# 7_Airframe-Sensors.net
KiCad netlist of a schematic drawn in Altium Designer
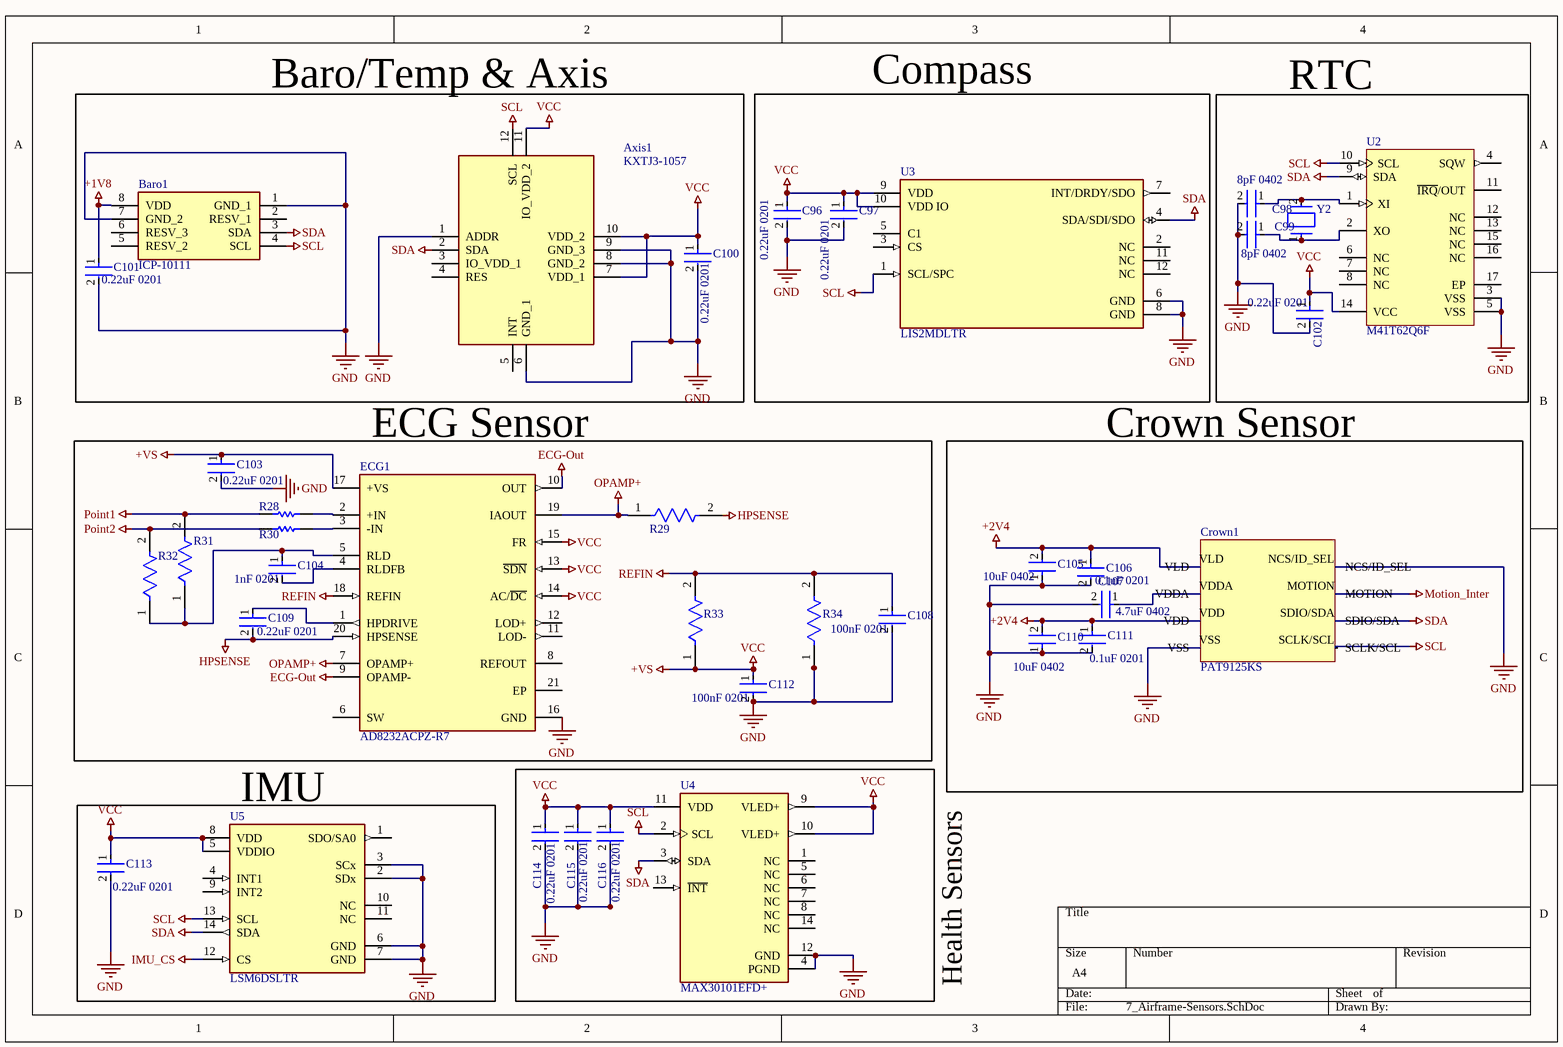
[diagram p0: 7_Airframe-Sensors.SchDoc]

(export (version "E")
  (design (tool "Eeschema 10.0.6"))
  (components
    (comp (ref "Axis1")
      (value "KXTJ3-1057")
      (footprint "SamacSys:2X2X0.9MMLGA")
      (description "Accelerometer")
      (fields (field (name "MOUSER PART NUMBER") "912-KXTJ3-1057"))
      (libsource (lib "*") (part "KXTJ3-1057"))
    )
    (comp (ref "Baro1")
      (value "ICP-10111")
      (footprint "SamacSys:ICP10111")
      (description "Undefined or Miscellaneous")
      (fields (field (name "MOUSER PART NUMBER") "410-ICP-10111"))
      (libsource (lib "*") (part "ICP-10111"))
    )
    (comp (ref "C96")
      (value "0.22uF 0201")
      (footprint "FP-C0603-030-0_03-IPC_C")
      (description "Multilayer Ceramic Capacitors 220nF ±10% 6.3V X6S SMD 0201")
      (fields (field (name "TOLERANCE") "10%"))
      (libsource (lib "Altium Content Vault") (part "02cd4be3c70576c341d710602a673aa"))
    )
    (comp (ref "C97")
      (value "0.22uF 0201")
      (footprint "FP-C0603-030-0_03-IPC_C")
      (description "Multilayer Ceramic Capacitors 220nF ±10% 6.3V X6S SMD 0201")
      (fields (field (name "TOLERANCE") "10%"))
      (libsource (lib "Altium Content Vault") (part "02cd4be3c70576c341d710602a673aa"))
    )
    (comp (ref "C98")
      (value "8pF 0402")
      (footprint "FP-C0402C225M9PACTU-MFG")
      (description "CAP CER 2.2UF 6.3V X5R 0402")
      (fields (field (name "VOLTAGE") "6.3V") (field (name "TOLERANCE") "20%"))
      (libsource (lib "Altium Content Vault") (part "b4654b650e69147ec39a6b967a45e02"))
    )
    (comp (ref "C99")
      (value "8pF 0402")
      (footprint "FP-C0402C225M9PACTU-MFG")
      (description "CAP CER 2.2UF 6.3V X5R 0402")
      (fields (field (name "VOLTAGE") "6.3V") (field (name "TOLERANCE") "20%"))
      (libsource (lib "Altium Content Vault") (part "b4654b650e69147ec39a6b967a45e02"))
    )
    (comp (ref "C100")
      (value "0.22uF 0201")
      (footprint "FP-C0603-030-0_03-IPC_C")
      (description "Multilayer Ceramic Capacitors 220nF ±10% 6.3V X6S SMD 0201")
      (fields (field (name "TOLERANCE") "10%"))
      (libsource (lib "Altium Content Vault") (part "02cd4be3c70576c341d710602a673aa"))
    )
    (comp (ref "C101")
      (value "0.22uF 0201")
      (footprint "FP-C0603-030-0_03-IPC_C")
      (description "Multilayer Ceramic Capacitors 220nF ±10% 6.3V X6S SMD 0201")
      (fields (field (name "TOLERANCE") "10%"))
      (libsource (lib "Altium Content Vault") (part "02cd4be3c70576c341d710602a673aa"))
    )
    (comp (ref "C102")
      (value "0.22uF 0201")
      (footprint "FP-C0603-030-0_03-IPC_C")
      (description "Multilayer Ceramic Capacitors 220nF ±10% 6.3V X6S SMD 0201")
      (fields (field (name "TOLERANCE") "10%"))
      (libsource (lib "Altium Content Vault") (part "02cd4be3c70576c341d710602a673aa"))
    )
    (comp (ref "C103")
      (value "0.22uF 0201")
      (footprint "FP-C0603-030-0_03-IPC_C")
      (description "Multilayer Ceramic Capacitors 220nF ±10% 6.3V X6S SMD 0201")
      (fields (field (name "TOLERANCE") "10%"))
      (libsource (lib "Altium Content Vault") (part "02cd4be3c70576c341d710602a673aa"))
    )
    (comp (ref "C104")
      (value "1nF 0201")
      (footprint "FP-C0603-030-0_03-IPC_C")
      (description "Multilayer Ceramic Capacitors 220nF ±10% 6.3V X6S SMD 0201")
      (fields (field (name "TOLERANCE") "10%"))
      (libsource (lib "Altium Content Vault") (part "02cd4be3c70576c341d710602a673aa"))
    )
    (comp (ref "C105")
      (value "10uF 0402")
      (footprint "FP-C0402C225M9PACTU-MFG")
      (description "CAP CER 2.2UF 6.3V X5R 0402")
      (fields (field (name "VOLTAGE") "6.3V") (field (name "TOLERANCE") "20%"))
      (libsource (lib "Altium Content Vault") (part "b4654b650e69147ec39a6b967a45e02"))
    )
    (comp (ref "C106")
      (value "0.1uF 0201")
      (footprint "FP-C0603-030-0_03-IPC_C")
      (description "Multilayer Ceramic Capacitors 220nF ±10% 6.3V X6S SMD 0201")
      (fields (field (name "TOLERANCE") "10%"))
      (libsource (lib "Altium Content Vault") (part "02cd4be3c70576c341d710602a673aa"))
    )
    (comp (ref "C107")
      (value "4.7uF 0402")
      (footprint "FP-C0402C225M9PACTU-MFG")
      (description "CAP CER 2.2UF 6.3V X5R 0402")
      (fields (field (name "VOLTAGE") "6.3V") (field (name "TOLERANCE") "20%"))
      (libsource (lib "Altium Content Vault") (part "b4654b650e69147ec39a6b967a45e02"))
    )
    (comp (ref "C108")
      (value "100nF 0201")
      (footprint "FP-C0603-030-0_03-IPC_C")
      (description "Multilayer Ceramic Capacitors 220nF ±10% 6.3V X6S SMD 0201")
      (fields (field (name "TOLERANCE") "10%"))
      (libsource (lib "Altium Content Vault") (part "02cd4be3c70576c341d710602a673aa"))
    )
    (comp (ref "C109")
      (value "0.22uF 0201")
      (footprint "FP-C0603-030-0_03-IPC_C")
      (description "Multilayer Ceramic Capacitors 220nF ±10% 6.3V X6S SMD 0201")
      (fields (field (name "TOLERANCE") "10%"))
      (libsource (lib "Altium Content Vault") (part "02cd4be3c70576c341d710602a673aa"))
    )
    (comp (ref "C110")
      (value "10uF 0402")
      (footprint "FP-C0402C225M9PACTU-MFG")
      (description "CAP CER 2.2UF 6.3V X5R 0402")
      (fields (field (name "VOLTAGE") "6.3V") (field (name "TOLERANCE") "20%"))
      (libsource (lib "Altium Content Vault") (part "b4654b650e69147ec39a6b967a45e02"))
    )
    (comp (ref "C111")
      (value "0.1uF 0201")
      (footprint "FP-C0603-030-0_03-IPC_C")
      (description "Multilayer Ceramic Capacitors 220nF ±10% 6.3V X6S SMD 0201")
      (fields (field (name "TOLERANCE") "10%"))
      (libsource (lib "Altium Content Vault") (part "02cd4be3c70576c341d710602a673aa"))
    )
    (comp (ref "C112")
      (value "100nF 0201")
      (footprint "FP-C0603-030-0_03-IPC_C")
      (description "Multilayer Ceramic Capacitors 220nF ±10% 6.3V X6S SMD 0201")
      (fields (field (name "TOLERANCE") "10%"))
      (libsource (lib "Altium Content Vault") (part "02cd4be3c70576c341d710602a673aa"))
    )
    (comp (ref "C113")
      (value "0.22uF 0201")
      (footprint "FP-C0603-030-0_03-IPC_C")
      (description "Multilayer Ceramic Capacitors 220nF ±10% 6.3V X6S SMD 0201")
      (fields (field (name "TOLERANCE") "10%"))
      (libsource (lib "Altium Content Vault") (part "02cd4be3c70576c341d710602a673aa"))
    )
    (comp (ref "C114")
      (value "0.22uF 0201")
      (footprint "FP-C0603-030-0_03-IPC_C")
      (description "Multilayer Ceramic Capacitors 220nF ±10% 6.3V X6S SMD 0201")
      (fields (field (name "TOLERANCE") "10%"))
      (libsource (lib "Altium Content Vault") (part "02cd4be3c70576c341d710602a673aa"))
    )
    (comp (ref "C115")
      (value "0.22uF 0201")
      (footprint "FP-C0603-030-0_03-IPC_C")
      (description "Multilayer Ceramic Capacitors 220nF ±10% 6.3V X6S SMD 0201")
      (fields (field (name "TOLERANCE") "10%"))
      (libsource (lib "Altium Content Vault") (part "02cd4be3c70576c341d710602a673aa"))
    )
    (comp (ref "C116")
      (value "0.22uF 0201")
      (footprint "FP-C0603-030-0_03-IPC_C")
      (description "Multilayer Ceramic Capacitors 220nF ±10% 6.3V X6S SMD 0201")
      (fields (field (name "TOLERANCE") "10%"))
      (libsource (lib "Altium Content Vault") (part "02cd4be3c70576c341d710602a673aa"))
    )
    (comp (ref "Crown1")
      (value "PAT9125KS")
      (footprint "PAT9125KS-Footprint-1")
      (libsource (lib "Projects") (part "PAT9125KS-Symbol-1"))
    )
    (comp (ref "ECG1")
      (value "AD8232ACPZ-R7")
      (footprint "FP-CP-20-8-IPC_C")
      (description "IC ECG FRONT END 20LFCSP")
      (libsource (lib "Altium Content Vault") (part "1c637333606c892ebbd82e67949bb2a"))
    )
    (comp (ref "R28")
      (value "RC0402FR-07180KL")
      (footprint "RESC1005X40X25ML05T10")
      (description "Chip Resistor, 180 KOhm, +/- 1%, 62.5 mW, -55 to 155 degC, 0402 (1005 Metric), RoHS, Tape and Reel")
      (fields (field (name "TOLERANCE") "1%") (field (name "MANUFACTURER") "Basic Passives"))
      (libsource (lib "Altium Content Vault") (part "RES-2"))
    )
    (comp (ref "R29")
      (value "CR0402-JW-105GLF")
      (footprint "FP-CR0402-MFG")
      (description "Thick Film Chip Resistors 0402 1MΩ 0.0625W 5% 200ppm/°C")
      (fields (field (name "TOLERANCE") "5%"))
      (libsource (lib "Altium Content Vault") (part "1029c3af85768c4190bb7ad29bc67b5"))
    )
    (comp (ref "R30")
      (value "RC0402FR-07180KL")
      (footprint "RESC1005X40X25ML05T10")
      (description "Chip Resistor, 180 KOhm, +/- 1%, 62.5 mW, -55 to 155 degC, 0402 (1005 Metric), RoHS, Tape and Reel")
      (fields (field (name "TOLERANCE") "1%") (field (name "MANUFACTURER") "Basic Passives"))
      (libsource (lib "Altium Content Vault") (part "RES-2"))
    )
    (comp (ref "R31")
      (value "CR0402-JW-105GLF")
      (footprint "FP-CR0402-MFG")
      (description "Thick Film Chip Resistors 0402 1MΩ 0.0625W 5% 200ppm/°C")
      (fields (field (name "TOLERANCE") "5%"))
      (libsource (lib "Altium Content Vault") (part "1029c3af85768c4190bb7ad29bc67b5"))
    )
    (comp (ref "R32")
      (value "CR0402-JW-105GLF")
      (footprint "FP-CR0402-MFG")
      (description "Thick Film Chip Resistors 0402 1MΩ 0.0625W 5% 200ppm/°C")
      (fields (field (name "TOLERANCE") "5%"))
      (libsource (lib "Altium Content Vault") (part "1029c3af85768c4190bb7ad29bc67b5"))
    )
    (comp (ref "R33")
      (value "CR0402-JW-105GLF")
      (footprint "FP-CR0402-MFG")
      (description "Thick Film Chip Resistors 0402 10MΩ 0.0625W 5% 200ppm/°C")
      (fields (field (name "TOLERANCE") "5%"))
      (libsource (lib "Altium Content Vault") (part "1029c3af85768c4190bb7ad29bc67b5"))
    )
    (comp (ref "R34")
      (value "CR0402-JW-105GLF")
      (footprint "FP-CR0402-MFG")
      (description "Thick Film Chip Resistors 0402 10MΩ 0.0625W 5% 200ppm/°C")
      (fields (field (name "TOLERANCE") "5%"))
      (libsource (lib "Altium Content Vault") (part "1029c3af85768c4190bb7ad29bc67b5"))
    )
    (comp (ref "U2")
      (value "M41T62Q6F")
      (footprint "STM-QFN-16_V")
      (fields (field (name "MANUFACTURER") "STMicroelectronics"))
      (libsource (lib "Altium Content Vault") (part "STM-M41T62-QFN-16"))
    )
    (comp (ref "U3")
      (value "LIS2MDLTR")
      (footprint "FP-LGA-12-DM00170568-MFG")
      (description "SENSOR MR I2C/SPI 12LGA")
      (fields
        (field (name "OCTOPART") "https://octopart.com/lis2mdltr-stmicroelectronics-81117311")
        (field (name "MANUFACTURER") "STMicroelectronics")
      )
      (libsource (lib "Altium Content Vault") (part "91637d6a6da3cb2d69b1e7726cd74d2"))
    )
    (comp (ref "U4")
      (value "MAX30101EFD+")
      (footprint "FP-F143A5-1-MFG")
      (description "INTEGRATED OPTICAL SENSOR")
      (fields
        (field (name "MANUFACTURER") "Maxim Integrated")
        (field (name "OCTOPART") "https://octopart.com/max30101efd%2B-maxim+integrated-57054333")
      )
      (libsource (lib "Altium Content Vault") (part "7412f82398c18c21c59cad441ae59a4"))
    )
    (comp (ref "U5")
      (value "LSM6DSLTR")
      (footprint "FP-LGA-14L-DM00249496-MFG")
      (description "IMU ACCEL/GYRO I2C/SPI 14LGA")
      (fields
        (field (name "MANUFACTURER") "STMicroelectronics")
        (field (name "OCTOPART") "https://octopart.com/lsm6dsltr-stmicroelectronics-66358193")
      )
      (libsource (lib "Altium Content Vault") (part "4e27e7d1829efda5344af1708d65448"))
    )
    (comp (ref "Y2")
      (value "ABS07-120-32.768KHZ-T")
      (footprint "FP-ABS07-120-MFG")
      (description "CRYSTAL 32.7680KHZ 6PF SMD")
      (fields (field (name "TOLERANCE") "20ppm"))
      (libsource (lib "Altium Content Vault") (part "c23a69dc6c9e2f18f2079038eb95dd1"))
    )
  )
  (nets
    (net (code "1") (name "+1V8") (class "Default")
      (node (ref "Baro1") (pin "8") (pinfunction "VDD_8") (pintype "passive"))
      (node (ref "C101") (pin "1") (pinfunction "1_1") (pintype "passive"))
    )
    (net (code "2") (name "+2V4") (class "Default")
      (node (ref "C105") (pin "2") (pinfunction "2_2") (pintype "passive"))
      (node (ref "C106") (pin "1") (pinfunction "1_1") (pintype "passive"))
      (node (ref "C110") (pin "2") (pinfunction "2_2") (pintype "passive"))
      (node (ref "C111") (pin "1") (pinfunction "1_1") (pintype "passive"))
      (node (ref "Crown1") (pin "VDD") (pinfunction "VDD_VDD") (pintype "passive"))
      (node (ref "Crown1") (pin "VLD") (pinfunction "VLD_VLD") (pintype "passive"))
    )
    (net (code "3") (name "+VS") (class "Default")
      (node (ref "Axis1") (pin "10") (pinfunction "VDD_2_10") (pintype "passive"))
      (node (ref "Axis1") (pin "11") (pinfunction "IO_VDD_2_11") (pintype "passive"))
      (node (ref "Axis1") (pin "7") (pinfunction "VDD_1_7") (pintype "passive"))
      (node (ref "C100") (pin "1") (pinfunction "1_1") (pintype "passive"))
      (node (ref "C102") (pin "1") (pinfunction "1_1") (pintype "passive"))
      (node (ref "C103") (pin "1") (pinfunction "1_1") (pintype "passive"))
      (node (ref "C112") (pin "1") (pinfunction "1_1") (pintype "passive"))
      (node (ref "C113") (pin "1") (pinfunction "1_1") (pintype "passive"))
      (node (ref "C114") (pin "1") (pinfunction "1_1") (pintype "passive"))
      (node (ref "C115") (pin "1") (pinfunction "1_1") (pintype "passive"))
      (node (ref "C116") (pin "1") (pinfunction "1_1") (pintype "passive"))
      (node (ref "C96") (pin "1") (pinfunction "1_1") (pintype "passive"))
      (node (ref "C97") (pin "1") (pinfunction "1_1") (pintype "passive"))
      (node (ref "ECG1") (pin "13") (pinfunction "~{SDN}_13") (pintype "input"))
      (node (ref "ECG1") (pin "14") (pinfunction "AC/~{DC}_14") (pintype "input"))
      (node (ref "ECG1") (pin "15") (pinfunction "FR_15") (pintype "input"))
      (node (ref "ECG1") (pin "17") (pinfunction "+VS_17") (pintype "power_in"))
      (node (ref "R33") (pin "1") (pinfunction "1_1") (pintype "passive"))
      (node (ref "U2") (pin "14") (pinfunction "VCC_14") (pintype "power_in"))
      (node (ref "U3") (pin "10") (pinfunction "VDD_IO_10") (pintype "power_in"))
      (node (ref "U3") (pin "9") (pinfunction "VDD_9") (pintype "power_in"))
      (node (ref "U4") (pin "10") (pinfunction "VLED+_10") (pintype "output"))
      (node (ref "U4") (pin "11") (pinfunction "VDD_11") (pintype "power_in"))
      (node (ref "U4") (pin "9") (pinfunction "VLED+_9") (pintype "output"))
      (node (ref "U5") (pin "5") (pinfunction "VDDIO_5") (pintype "power_in"))
      (node (ref "U5") (pin "8") (pinfunction "VDD_8") (pintype "power_in"))
    )
    (net (code "4") (name "ECG-Out") (class "Default")
      (node (ref "ECG1") (pin "10") (pinfunction "OUT_10") (pintype "output"))
      (node (ref "ECG1") (pin "9") (pinfunction "OPAMP-_9") (pintype "tri_state"))
    )
    (net (code "5") (name "GND") (class "Default")
      (node (ref "Axis1") (pin "1") (pinfunction "ADDR_1") (pintype "passive"))
      (node (ref "Axis1") (pin "6") (pinfunction "GND_1_6") (pintype "passive"))
      (node (ref "Axis1") (pin "8") (pinfunction "GND_2_8") (pintype "passive"))
      (node (ref "Axis1") (pin "9") (pinfunction "GND_3_9") (pintype "passive"))
      (node (ref "Baro1") (pin "1") (pinfunction "GND_1_1") (pintype "passive"))
      (node (ref "Baro1") (pin "7") (pinfunction "GND_2_7") (pintype "passive"))
      (node (ref "C100") (pin "2") (pinfunction "2_2") (pintype "passive"))
      (node (ref "C101") (pin "2") (pinfunction "2_2") (pintype "passive"))
      (node (ref "C102") (pin "2") (pinfunction "2_2") (pintype "passive"))
      (node (ref "C103") (pin "2") (pinfunction "2_2") (pintype "passive"))
      (node (ref "C105") (pin "1") (pinfunction "1_1") (pintype "passive"))
      (node (ref "C106") (pin "2") (pinfunction "2_2") (pintype "passive"))
      (node (ref "C107") (pin "2") (pinfunction "2_2") (pintype "passive"))
      (node (ref "C108") (pin "2") (pinfunction "2_2") (pintype "passive"))
      (node (ref "C110") (pin "1") (pinfunction "1_1") (pintype "passive"))
      (node (ref "C111") (pin "2") (pinfunction "2_2") (pintype "passive"))
      (node (ref "C112") (pin "2") (pinfunction "2_2") (pintype "passive"))
      (node (ref "C113") (pin "2") (pinfunction "2_2") (pintype "passive"))
      (node (ref "C114") (pin "2") (pinfunction "2_2") (pintype "passive"))
      (node (ref "C115") (pin "2") (pinfunction "2_2") (pintype "passive"))
      (node (ref "C116") (pin "2") (pinfunction "2_2") (pintype "passive"))
      (node (ref "C96") (pin "2") (pinfunction "2_2") (pintype "passive"))
      (node (ref "C97") (pin "2") (pinfunction "2_2") (pintype "passive"))
      (node (ref "C98") (pin "2") (pinfunction "2_2") (pintype "passive"))
      (node (ref "C99") (pin "2") (pinfunction "2_2") (pintype "passive"))
      (node (ref "Crown1") (pin "NCS/ID_SEL") (pinfunction "NCS/ID_SEL_NCS/ID_SEL") (pintype "passive"))
      (node (ref "Crown1") (pin "VSS") (pinfunction "VSS_VSS") (pintype "passive"))
      (node (ref "ECG1") (pin "16") (pinfunction "GND_16") (pintype "power_in"))
      (node (ref "R34") (pin "1") (pinfunction "1_1") (pintype "passive"))
      (node (ref "U2") (pin "3") (pinfunction "VSS_3") (pintype "power_in"))
      (node (ref "U2") (pin "5") (pinfunction "VSS_5") (pintype "power_in"))
      (node (ref "U3") (pin "6") (pinfunction "GND_6") (pintype "power_in"))
      (node (ref "U3") (pin "8") (pinfunction "GND_8") (pintype "power_in"))
      (node (ref "U4") (pin "12") (pinfunction "GND_12") (pintype "power_in"))
      (node (ref "U4") (pin "4") (pinfunction "PGND_4") (pintype "power_in"))
      (node (ref "U5") (pin "2") (pinfunction "SDx_2") (pintype "passive"))
      (node (ref "U5") (pin "3") (pinfunction "SCx_3") (pintype "passive"))
      (node (ref "U5") (pin "6") (pinfunction "GND_6") (pintype "power_in"))
      (node (ref "U5") (pin "7") (pinfunction "GND_7") (pintype "power_in"))
    )
    (net (code "6") (name "HPSENSE") (class "Default")
      (node (ref "C109") (pin "2") (pinfunction "2_2") (pintype "passive"))
      (node (ref "ECG1") (pin "20") (pinfunction "HPSENSE_20") (pintype "input"))
      (node (ref "R29") (pin "2") (pinfunction "2_2") (pintype "passive"))
    )
    (net (code "7") (name "IMU_CS") (class "Default")
      (node (ref "U5") (pin "12") (pinfunction "CS_12") (pintype "input"))
    )
    (net (code "8") (name "Motion_Inter") (class "Default")
      (node (ref "Crown1") (pin "MOTION") (pinfunction "MOTION_MOTION") (pintype "passive"))
    )
    (net (code "9") (name "Net-(C107-Pad1)") (class "Default")
      (node (ref "C107") (pin "1") (pinfunction "1_1") (pintype "passive"))
      (node (ref "Crown1") (pin "VDDA") (pinfunction "VDDA_VDDA") (pintype "passive"))
    )
    (net (code "10") (name "Net-(ECG1-+IN)") (class "Default")
      (node (ref "ECG1") (pin "2") (pinfunction "+IN_2") (pintype "tri_state"))
      (node (ref "R28") (pin "2") (pinfunction "2_2") (pintype "passive"))
    )
    (net (code "11") (name "Net-(ECG1--IN)") (class "Default")
      (node (ref "ECG1") (pin "3") (pinfunction "-IN_3") (pintype "tri_state"))
      (node (ref "R30") (pin "2") (pinfunction "2_2") (pintype "passive"))
    )
    (net (code "12") (name "Net-(ECG1-HPDRIVE)") (class "Default")
      (node (ref "C109") (pin "1") (pinfunction "1_1") (pintype "passive"))
      (node (ref "ECG1") (pin "1") (pinfunction "HPDRIVE_1") (pintype "output"))
    )
    (net (code "13") (name "Net-(ECG1-RLD)") (class "Default")
      (node (ref "C104") (pin "1") (pinfunction "1_1") (pintype "passive"))
      (node (ref "ECG1") (pin "5") (pinfunction "RLD_5") (pintype "passive"))
      (node (ref "R31") (pin "1") (pinfunction "1_1") (pintype "passive"))
      (node (ref "R32") (pin "1") (pinfunction "1_1") (pintype "passive"))
    )
    (net (code "14") (name "Net-(ECG1-RLDFB)") (class "Default")
      (node (ref "C104") (pin "2") (pinfunction "2_2") (pintype "passive"))
      (node (ref "ECG1") (pin "4") (pinfunction "RLDFB_4") (pintype "passive"))
    )
    (net (code "15") (name "Net-(U2-XI)") (class "Default")
      (node (ref "C98") (pin "1") (pinfunction "1_1") (pintype "passive"))
      (node (ref "U2") (pin "1") (pinfunction "XI_1") (pintype "input"))
      (node (ref "Y2") (pin "2") (pinfunction "2_2") (pintype "passive"))
    )
    (net (code "16") (name "Net-(U2-XO)") (class "Default")
      (node (ref "C99") (pin "1") (pinfunction "1_1") (pintype "passive"))
      (node (ref "U2") (pin "2") (pinfunction "XO_2") (pintype "passive"))
      (node (ref "Y2") (pin "1") (pinfunction "1_1") (pintype "passive"))
    )
    (net (code "17") (name "OPAMP+") (class "Default")
      (node (ref "ECG1") (pin "19") (pinfunction "IAOUT_19") (pintype "passive"))
      (node (ref "ECG1") (pin "7") (pinfunction "OPAMP+_7") (pintype "tri_state"))
      (node (ref "R29") (pin "1") (pinfunction "1_1") (pintype "passive"))
    )
    (net (code "18") (name "Point1") (class "Default")
      (node (ref "R28") (pin "1") (pinfunction "1_1") (pintype "passive"))
      (node (ref "R31") (pin "2") (pinfunction "2_2") (pintype "passive"))
    )
    (net (code "19") (name "Point2") (class "Default")
      (node (ref "R30") (pin "1") (pinfunction "1_1") (pintype "passive"))
      (node (ref "R32") (pin "2") (pinfunction "2_2") (pintype "passive"))
    )
    (net (code "20") (name "REFIN") (class "Default")
      (node (ref "C108") (pin "1") (pinfunction "1_1") (pintype "passive"))
      (node (ref "ECG1") (pin "18") (pinfunction "REFIN_18") (pintype "input"))
      (node (ref "R33") (pin "2") (pinfunction "2_2") (pintype "passive"))
      (node (ref "R34") (pin "2") (pinfunction "2_2") (pintype "passive"))
    )
    (net (code "21") (name "SCL") (class "Default")
      (node (ref "Axis1") (pin "12") (pinfunction "SCL_12") (pintype "passive"))
      (node (ref "Baro1") (pin "4") (pinfunction "SCL_4") (pintype "passive"))
      (node (ref "Crown1") (pin "SCLK/SCL") (pinfunction "SCLK/SCL_SCLK/SCL") (pintype "passive"))
      (node (ref "U2") (pin "10") (pinfunction "SCL_10") (pintype "input"))
      (node (ref "U3") (pin "1") (pinfunction "SCL/SPC_1") (pintype "input"))
      (node (ref "U4") (pin "2") (pinfunction "SCL_2") (pintype "input"))
      (node (ref "U5") (pin "13") (pinfunction "SCL_13") (pintype "input"))
    )
    (net (code "22") (name "SDA") (class "Default")
      (node (ref "Axis1") (pin "2") (pinfunction "SDA_2") (pintype "passive"))
      (node (ref "Baro1") (pin "3") (pinfunction "SDA_3") (pintype "passive"))
      (node (ref "Crown1") (pin "SDIO/SDA") (pinfunction "SDIO/SDA_SDIO/SDA") (pintype "passive"))
      (node (ref "U2") (pin "9") (pinfunction "SDA_9") (pintype "bidirectional"))
      (node (ref "U3") (pin "4") (pinfunction "SDA/SDI/SDO_4") (pintype "bidirectional"))
      (node (ref "U4") (pin "3") (pinfunction "SDA_3") (pintype "bidirectional"))
      (node (ref "U5") (pin "14") (pinfunction "SDA_14") (pintype "output"))
    )
    (net (code "23") (name "unconnected-(Axis1-INT-Pad5)") (class "Default")
      (node (ref "Axis1") (pin "5") (pinfunction "INT_5") (pintype "passive"))
    )
    (net (code "24") (name "unconnected-(Axis1-IO_VDD_1-Pad3)") (class "Default")
      (node (ref "Axis1") (pin "3") (pinfunction "IO_VDD_1_3") (pintype "passive"))
    )
    (net (code "25") (name "unconnected-(Axis1-RES-Pad4)") (class "Default")
      (node (ref "Axis1") (pin "4") (pinfunction "RES_4") (pintype "passive"))
    )
    (net (code "26") (name "unconnected-(Baro1-RESV_1-Pad2)") (class "Default")
      (node (ref "Baro1") (pin "2") (pinfunction "RESV_1_2") (pintype "passive"))
    )
    (net (code "27") (name "unconnected-(Baro1-RESV_2-Pad5)") (class "Default")
      (node (ref "Baro1") (pin "5") (pinfunction "RESV_2_5") (pintype "passive"))
    )
    (net (code "28") (name "unconnected-(Baro1-RESV_3-Pad6)") (class "Default")
      (node (ref "Baro1") (pin "6") (pinfunction "RESV_3_6") (pintype "passive"))
    )
    (net (code "29") (name "unconnected-(ECG1-EP-Pad21)") (class "Default")
      (node (ref "ECG1") (pin "21") (pinfunction "EP_21") (pintype "power_in"))
    )
    (net (code "30") (name "unconnected-(ECG1-LOD+-Pad12)") (class "Default")
      (node (ref "ECG1") (pin "12") (pinfunction "LOD+_12") (pintype "output"))
    )
    (net (code "31") (name "unconnected-(ECG1-LOD--Pad11)") (class "Default")
      (node (ref "ECG1") (pin "11") (pinfunction "LOD-_11") (pintype "output"))
    )
    (net (code "32") (name "unconnected-(ECG1-REFOUT-Pad8)") (class "Default")
      (node (ref "ECG1") (pin "8") (pinfunction "REFOUT_8") (pintype "passive"))
    )
    (net (code "33") (name "unconnected-(ECG1-SW-Pad6)") (class "Default")
      (node (ref "ECG1") (pin "6") (pinfunction "SW_6") (pintype "passive"))
    )
    (net (code "34") (name "unconnected-(U2-EP-Pad17)") (class "Default")
      (node (ref "U2") (pin "17") (pinfunction "EP_17") (pintype "passive"))
    )
    (net (code "35") (name "unconnected-(U2-NC-Pad6)") (class "Default")
      (node (ref "U2") (pin "6") (pinfunction "NC_6") (pintype "passive"))
    )
    (net (code "36") (name "unconnected-(U2-NC-Pad7)") (class "Default")
      (node (ref "U2") (pin "7") (pinfunction "NC_7") (pintype "passive"))
    )
    (net (code "37") (name "unconnected-(U2-NC-Pad8)") (class "Default")
      (node (ref "U2") (pin "8") (pinfunction "NC_8") (pintype "passive"))
    )
    (net (code "38") (name "unconnected-(U2-NC-Pad12)") (class "Default")
      (node (ref "U2") (pin "12") (pinfunction "NC_12") (pintype "passive"))
    )
    (net (code "39") (name "unconnected-(U2-NC-Pad13)") (class "Default")
      (node (ref "U2") (pin "13") (pinfunction "NC_13") (pintype "passive"))
    )
    (net (code "40") (name "unconnected-(U2-NC-Pad15)") (class "Default")
      (node (ref "U2") (pin "15") (pinfunction "NC_15") (pintype "passive"))
    )
    (net (code "41") (name "unconnected-(U2-NC-Pad16)") (class "Default")
      (node (ref "U2") (pin "16") (pinfunction "NC_16") (pintype "passive"))
    )
    (net (code "42") (name "unconnected-(U2-SQW-Pad4)") (class "Default")
      (node (ref "U2") (pin "4") (pinfunction "SQW_4") (pintype "output"))
    )
    (net (code "43") (name "unconnected-(U2-~{IRQ}{slash}OUT-Pad11)") (class "Default")
      (node (ref "U2") (pin "11") (pinfunction "~{IRQ}/OUT_11") (pintype "open_collector"))
    )
    (net (code "44") (name "unconnected-(U3-C1-Pad5)") (class "Default")
      (node (ref "U3") (pin "5") (pinfunction "C1_5") (pintype "passive"))
    )
    (net (code "45") (name "unconnected-(U3-CS-Pad3)") (class "Default")
      (node (ref "U3") (pin "3") (pinfunction "CS_3") (pintype "input"))
    )
    (net (code "46") (name "unconnected-(U3-INT{slash}DRDY{slash}SDO-Pad7)") (class "Default")
      (node (ref "U3") (pin "7") (pinfunction "INT/DRDY/SDO_7") (pintype "output"))
    )
    (net (code "47") (name "unconnected-(U3-NC-Pad2)") (class "Default")
      (node (ref "U3") (pin "2") (pinfunction "NC_2") (pintype "passive"))
    )
    (net (code "48") (name "unconnected-(U3-NC-Pad11)") (class "Default")
      (node (ref "U3") (pin "11") (pinfunction "NC_11") (pintype "passive"))
    )
    (net (code "49") (name "unconnected-(U3-NC-Pad12)") (class "Default")
      (node (ref "U3") (pin "12") (pinfunction "NC_12") (pintype "passive"))
    )
    (net (code "50") (name "unconnected-(U4-NC-Pad1)") (class "Default")
      (node (ref "U4") (pin "1") (pinfunction "NC_1") (pintype "passive"))
    )
    (net (code "51") (name "unconnected-(U4-NC-Pad5)") (class "Default")
      (node (ref "U4") (pin "5") (pinfunction "NC_5") (pintype "passive"))
    )
    (net (code "52") (name "unconnected-(U4-NC-Pad6)") (class "Default")
      (node (ref "U4") (pin "6") (pinfunction "NC_6") (pintype "passive"))
    )
    (net (code "53") (name "unconnected-(U4-NC-Pad7)") (class "Default")
      (node (ref "U4") (pin "7") (pinfunction "NC_7") (pintype "passive"))
    )
    (net (code "54") (name "unconnected-(U4-NC-Pad8)") (class "Default")
      (node (ref "U4") (pin "8") (pinfunction "NC_8") (pintype "passive"))
    )
    (net (code "55") (name "unconnected-(U4-NC-Pad14)") (class "Default")
      (node (ref "U4") (pin "14") (pinfunction "NC_14") (pintype "passive"))
    )
    (net (code "56") (name "unconnected-(U4-~{INT}-Pad13)") (class "Default")
      (node (ref "U4") (pin "13") (pinfunction "~{INT}_13") (pintype "input"))
    )
    (net (code "57") (name "unconnected-(U5-INT1-Pad4)") (class "Default")
      (node (ref "U5") (pin "4") (pinfunction "INT1_4") (pintype "input"))
    )
    (net (code "58") (name "unconnected-(U5-INT2-Pad9)") (class "Default")
      (node (ref "U5") (pin "9") (pinfunction "INT2_9") (pintype "input"))
    )
    (net (code "59") (name "unconnected-(U5-NC-Pad10)") (class "Default")
      (node (ref "U5") (pin "10") (pinfunction "NC_10") (pintype "passive"))
    )
    (net (code "60") (name "unconnected-(U5-NC-Pad11)") (class "Default")
      (node (ref "U5") (pin "11") (pinfunction "NC_11") (pintype "passive"))
    )
    (net (code "61") (name "unconnected-(U5-SDO{slash}SA0-Pad1)") (class "Default")
      (node (ref "U5") (pin "1") (pinfunction "SDO/SA0_1") (pintype "output"))
    )
  )
)
